# Main.net
KiCad netlist of a schematic drawn in Altium Designer
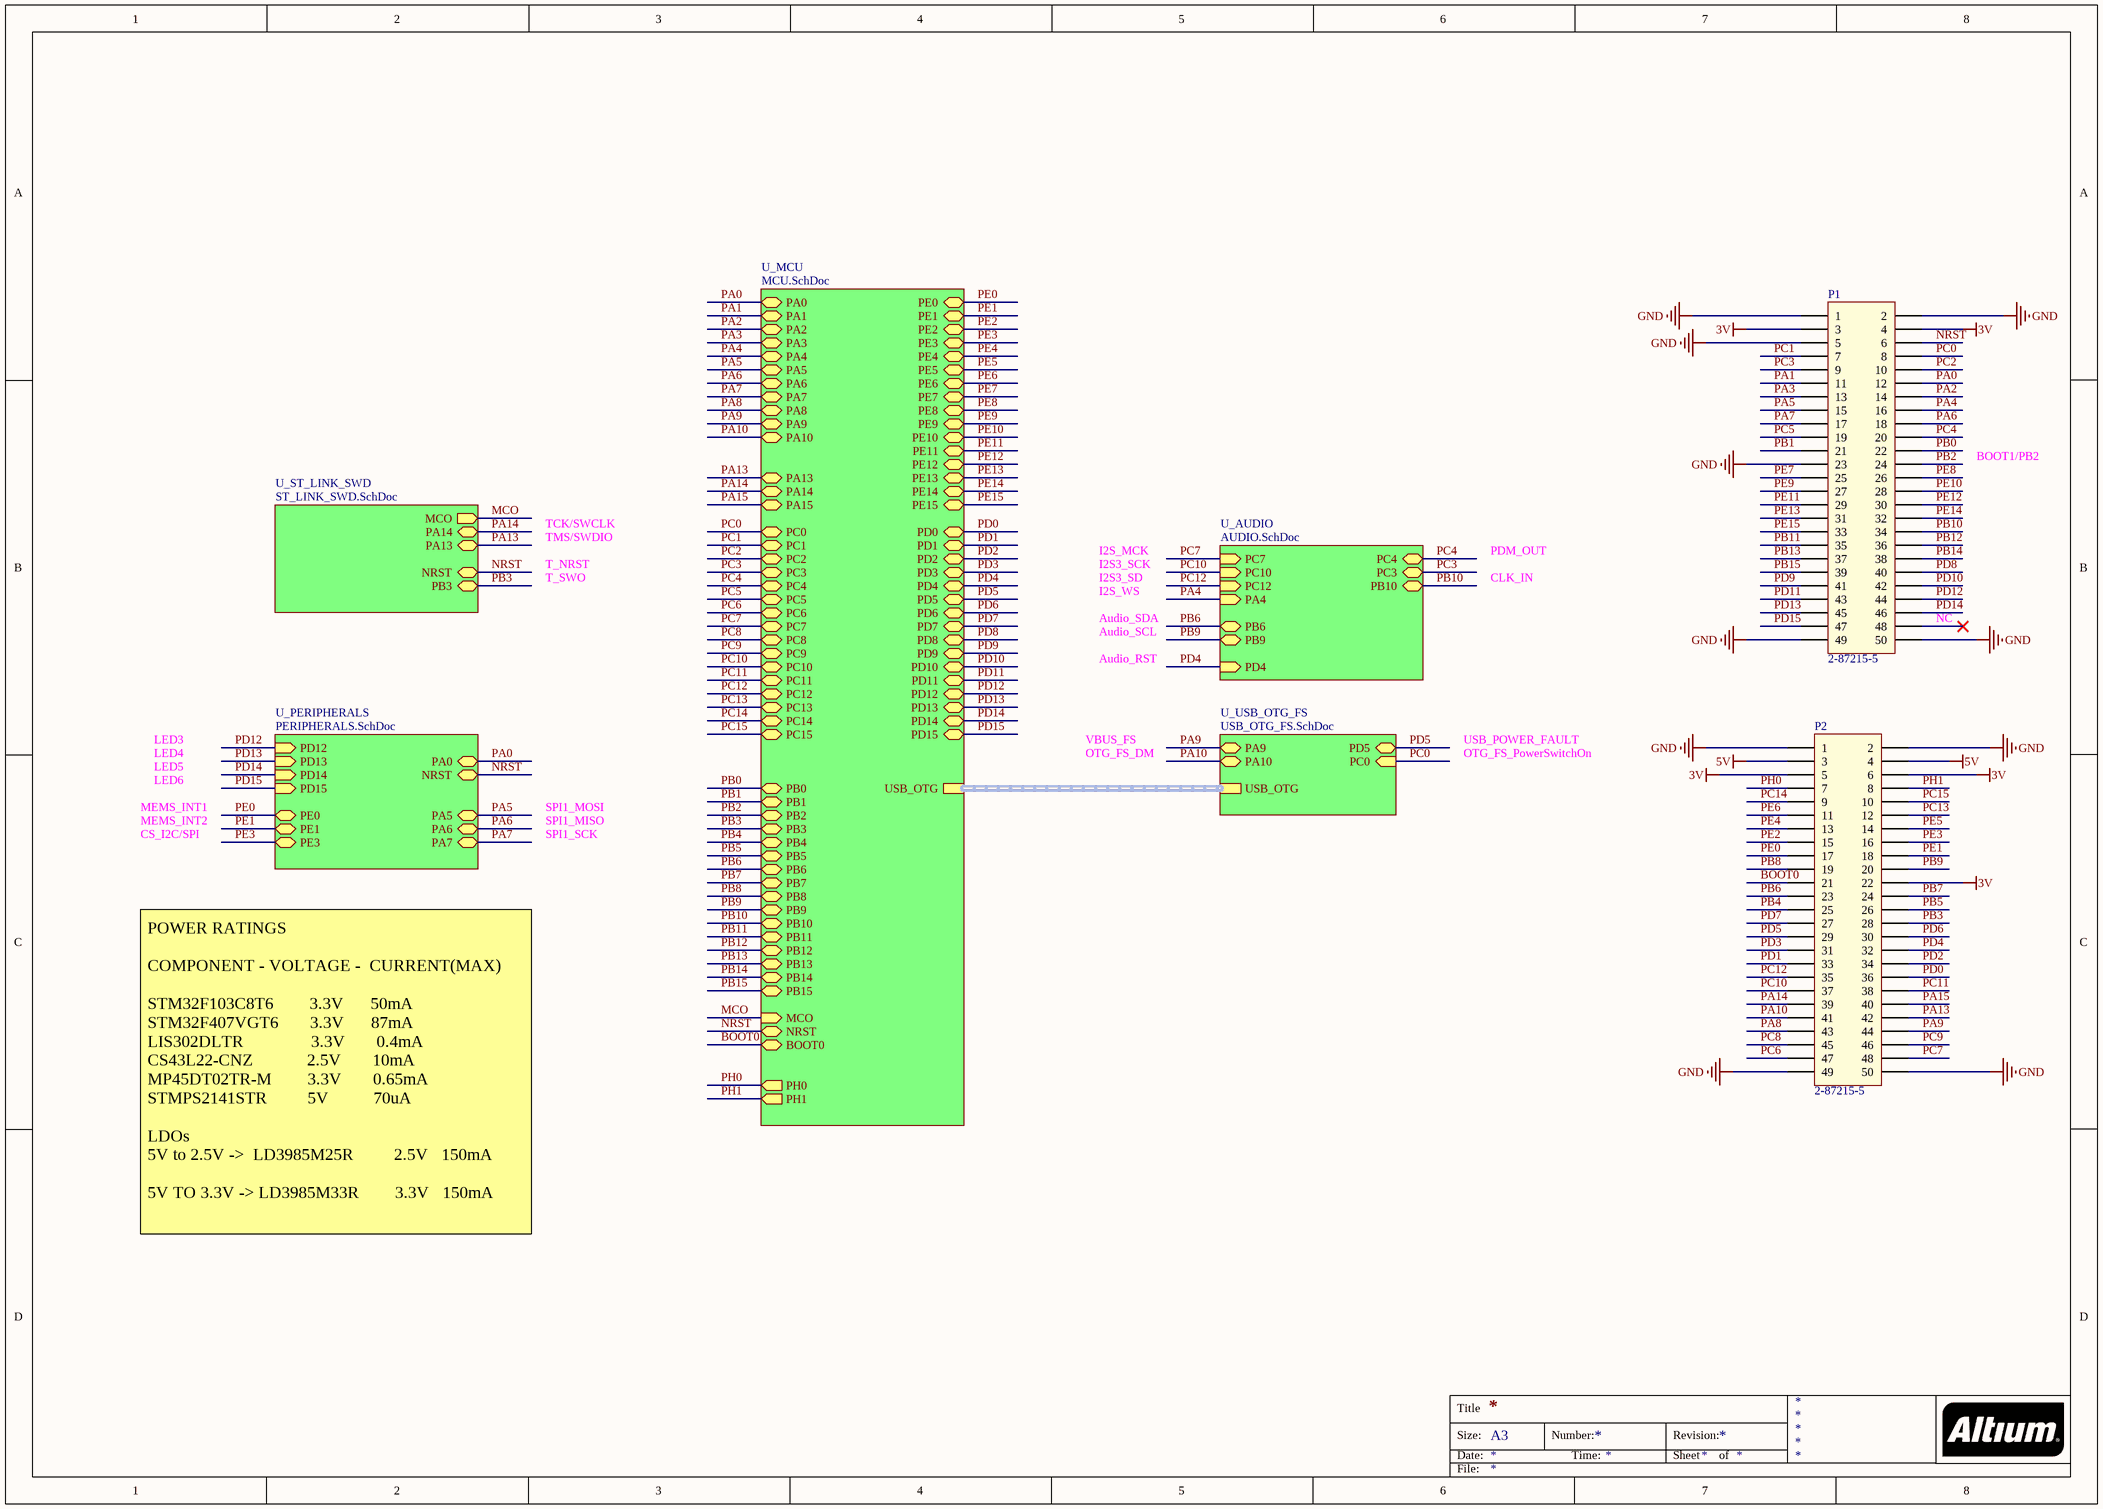
[diagram p0: Main.SchDoc]

(export (version "E")
  (design (tool "Eeschema 10.0.6"))
  (components
    (comp (ref "P1")
      (value "2-87215-5")
      (footprint "HEADER 25x2")
      (fields (field (name "MANUFACTURER") "TE Connectivity (Tyco Electronics)"))
      (libsource (lib "STM32F4DISCOVERY") (part "2-87215-5"))
    )
    (comp (ref "P2")
      (value "2-87215-5")
      (footprint "HEADER 25x2")
      (fields (field (name "MANUFACTURER") "TE Connectivity (Tyco Electronics)"))
      (libsource (lib "STM32F4DISCOVERY") (part "2-87215-5"))
    )
  )
  (nets
    (net (code "1") (name "/BOOT0") (class "Default")
      (node (ref "P2") (pin "21") (pinfunction "21_21") (pintype "passive"))
    )
    (net (code "3") (name "/NRST") (class "Default")
      (node (ref "P1") (pin "6") (pinfunction "6_6") (pintype "passive"))
    )
    (net (code "4") (name "/PA0") (class "Default")
      (node (ref "P1") (pin "12") (pinfunction "12_12") (pintype "passive"))
    )
    (net (code "5") (name "/PA1") (class "Default")
      (node (ref "P1") (pin "11") (pinfunction "11_11") (pintype "passive"))
    )
    (net (code "6") (name "/PA2") (class "Default")
      (node (ref "P1") (pin "14") (pinfunction "14_14") (pintype "passive"))
    )
    (net (code "7") (name "/PA3") (class "Default")
      (node (ref "P1") (pin "13") (pinfunction "13_13") (pintype "passive"))
    )
    (net (code "8") (name "/PA4") (class "Default")
      (node (ref "P1") (pin "16") (pinfunction "16_16") (pintype "passive"))
    )
    (net (code "9") (name "/PA5") (class "Default")
      (node (ref "P1") (pin "15") (pinfunction "15_15") (pintype "passive"))
    )
    (net (code "10") (name "/PA6") (class "Default")
      (node (ref "P1") (pin "18") (pinfunction "18_18") (pintype "passive"))
    )
    (net (code "11") (name "/PA7") (class "Default")
      (node (ref "P1") (pin "17") (pinfunction "17_17") (pintype "passive"))
    )
    (net (code "12") (name "/PA8") (class "Default")
      (node (ref "P2") (pin "43") (pinfunction "43_43") (pintype "passive"))
    )
    (net (code "13") (name "/PA9") (class "Default")
      (node (ref "P2") (pin "44") (pinfunction "44_44") (pintype "passive"))
    )
    (net (code "14") (name "/PA10") (class "Default")
      (node (ref "P2") (pin "41") (pinfunction "41_41") (pintype "passive"))
    )
    (net (code "15") (name "/PA13") (class "Default")
      (node (ref "P2") (pin "42") (pinfunction "42_42") (pintype "passive"))
    )
    (net (code "16") (name "/PA14") (class "Default")
      (node (ref "P2") (pin "39") (pinfunction "39_39") (pintype "passive"))
    )
    (net (code "17") (name "/PA15") (class "Default")
      (node (ref "P2") (pin "40") (pinfunction "40_40") (pintype "passive"))
    )
    (net (code "18") (name "/PB0") (class "Default")
      (node (ref "P1") (pin "22") (pinfunction "22_22") (pintype "passive"))
    )
    (net (code "19") (name "/PB1") (class "Default")
      (node (ref "P1") (pin "21") (pinfunction "21_21") (pintype "passive"))
    )
    (net (code "20") (name "/PB2") (class "Default")
      (node (ref "P1") (pin "24") (pinfunction "24_24") (pintype "passive"))
    )
    (net (code "21") (name "/PB3") (class "Default")
      (node (ref "P2") (pin "28") (pinfunction "28_28") (pintype "passive"))
    )
    (net (code "22") (name "/PB4") (class "Default")
      (node (ref "P2") (pin "25") (pinfunction "25_25") (pintype "passive"))
    )
    (net (code "23") (name "/PB5") (class "Default")
      (node (ref "P2") (pin "26") (pinfunction "26_26") (pintype "passive"))
    )
    (net (code "24") (name "/PB6") (class "Default")
      (node (ref "P2") (pin "23") (pinfunction "23_23") (pintype "passive"))
    )
    (net (code "25") (name "/PB7") (class "Default")
      (node (ref "P2") (pin "24") (pinfunction "24_24") (pintype "passive"))
    )
    (net (code "26") (name "/PB8") (class "Default")
      (node (ref "P2") (pin "19") (pinfunction "19_19") (pintype "passive"))
    )
    (net (code "27") (name "/PB9") (class "Default")
      (node (ref "P2") (pin "20") (pinfunction "20_20") (pintype "passive"))
    )
    (net (code "28") (name "/PB10") (class "Default")
      (node (ref "P1") (pin "34") (pinfunction "34_34") (pintype "passive"))
    )
    (net (code "29") (name "/PB11") (class "Default")
      (node (ref "P1") (pin "35") (pinfunction "35_35") (pintype "passive"))
    )
    (net (code "30") (name "/PB12") (class "Default")
      (node (ref "P1") (pin "36") (pinfunction "36_36") (pintype "passive"))
    )
    (net (code "31") (name "/PB13") (class "Default")
      (node (ref "P1") (pin "37") (pinfunction "37_37") (pintype "passive"))
    )
    (net (code "32") (name "/PB14") (class "Default")
      (node (ref "P1") (pin "38") (pinfunction "38_38") (pintype "passive"))
    )
    (net (code "33") (name "/PB15") (class "Default")
      (node (ref "P1") (pin "39") (pinfunction "39_39") (pintype "passive"))
    )
    (net (code "34") (name "/PC0") (class "Default")
      (node (ref "P1") (pin "8") (pinfunction "8_8") (pintype "passive"))
    )
    (net (code "35") (name "/PC1") (class "Default")
      (node (ref "P1") (pin "7") (pinfunction "7_7") (pintype "passive"))
    )
    (net (code "36") (name "/PC2") (class "Default")
      (node (ref "P1") (pin "10") (pinfunction "10_10") (pintype "passive"))
    )
    (net (code "37") (name "/PC3") (class "Default")
      (node (ref "P1") (pin "9") (pinfunction "9_9") (pintype "passive"))
    )
    (net (code "38") (name "/PC4") (class "Default")
      (node (ref "P1") (pin "20") (pinfunction "20_20") (pintype "passive"))
    )
    (net (code "39") (name "/PC5") (class "Default")
      (node (ref "P1") (pin "19") (pinfunction "19_19") (pintype "passive"))
    )
    (net (code "40") (name "/PC6") (class "Default")
      (node (ref "P2") (pin "47") (pinfunction "47_47") (pintype "passive"))
    )
    (net (code "41") (name "/PC7") (class "Default")
      (node (ref "P2") (pin "48") (pinfunction "48_48") (pintype "passive"))
    )
    (net (code "42") (name "/PC8") (class "Default")
      (node (ref "P2") (pin "45") (pinfunction "45_45") (pintype "passive"))
    )
    (net (code "43") (name "/PC9") (class "Default")
      (node (ref "P2") (pin "46") (pinfunction "46_46") (pintype "passive"))
    )
    (net (code "44") (name "/PC10") (class "Default")
      (node (ref "P2") (pin "37") (pinfunction "37_37") (pintype "passive"))
    )
    (net (code "45") (name "/PC11") (class "Default")
      (node (ref "P2") (pin "38") (pinfunction "38_38") (pintype "passive"))
    )
    (net (code "46") (name "/PC12") (class "Default")
      (node (ref "P2") (pin "35") (pinfunction "35_35") (pintype "passive"))
    )
    (net (code "47") (name "/PC13") (class "Default")
      (node (ref "P2") (pin "12") (pinfunction "12_12") (pintype "passive"))
    )
    (net (code "48") (name "/PC14") (class "Default")
      (node (ref "P2") (pin "9") (pinfunction "9_9") (pintype "passive"))
    )
    (net (code "49") (name "/PC15") (class "Default")
      (node (ref "P2") (pin "10") (pinfunction "10_10") (pintype "passive"))
    )
    (net (code "50") (name "/PD0") (class "Default")
      (node (ref "P2") (pin "36") (pinfunction "36_36") (pintype "passive"))
    )
    (net (code "51") (name "/PD1") (class "Default")
      (node (ref "P2") (pin "33") (pinfunction "33_33") (pintype "passive"))
    )
    (net (code "52") (name "/PD2") (class "Default")
      (node (ref "P2") (pin "34") (pinfunction "34_34") (pintype "passive"))
    )
    (net (code "53") (name "/PD3") (class "Default")
      (node (ref "P2") (pin "31") (pinfunction "31_31") (pintype "passive"))
    )
    (net (code "54") (name "/PD4") (class "Default")
      (node (ref "P2") (pin "32") (pinfunction "32_32") (pintype "passive"))
    )
    (net (code "55") (name "/PD5") (class "Default")
      (node (ref "P2") (pin "29") (pinfunction "29_29") (pintype "passive"))
    )
    (net (code "56") (name "/PD6") (class "Default")
      (node (ref "P2") (pin "30") (pinfunction "30_30") (pintype "passive"))
    )
    (net (code "57") (name "/PD7") (class "Default")
      (node (ref "P2") (pin "27") (pinfunction "27_27") (pintype "passive"))
    )
    (net (code "58") (name "/PD8") (class "Default")
      (node (ref "P1") (pin "40") (pinfunction "40_40") (pintype "passive"))
    )
    (net (code "59") (name "/PD9") (class "Default")
      (node (ref "P1") (pin "41") (pinfunction "41_41") (pintype "passive"))
    )
    (net (code "60") (name "/PD10") (class "Default")
      (node (ref "P1") (pin "42") (pinfunction "42_42") (pintype "passive"))
    )
    (net (code "61") (name "/PD11") (class "Default")
      (node (ref "P1") (pin "43") (pinfunction "43_43") (pintype "passive"))
    )
    (net (code "62") (name "/PD12") (class "Default")
      (node (ref "P1") (pin "44") (pinfunction "44_44") (pintype "passive"))
    )
    (net (code "63") (name "/PD13") (class "Default")
      (node (ref "P1") (pin "45") (pinfunction "45_45") (pintype "passive"))
    )
    (net (code "64") (name "/PD14") (class "Default")
      (node (ref "P1") (pin "46") (pinfunction "46_46") (pintype "passive"))
    )
    (net (code "65") (name "/PD15") (class "Default")
      (node (ref "P1") (pin "47") (pinfunction "47_47") (pintype "passive"))
    )
    (net (code "66") (name "/PE0") (class "Default")
      (node (ref "P2") (pin "17") (pinfunction "17_17") (pintype "passive"))
    )
    (net (code "67") (name "/PE1") (class "Default")
      (node (ref "P2") (pin "18") (pinfunction "18_18") (pintype "passive"))
    )
    (net (code "68") (name "/PE2") (class "Default")
      (node (ref "P2") (pin "15") (pinfunction "15_15") (pintype "passive"))
    )
    (net (code "69") (name "/PE3") (class "Default")
      (node (ref "P2") (pin "16") (pinfunction "16_16") (pintype "passive"))
    )
    (net (code "70") (name "/PE4") (class "Default")
      (node (ref "P2") (pin "13") (pinfunction "13_13") (pintype "passive"))
    )
    (net (code "71") (name "/PE5") (class "Default")
      (node (ref "P2") (pin "14") (pinfunction "14_14") (pintype "passive"))
    )
    (net (code "72") (name "/PE6") (class "Default")
      (node (ref "P2") (pin "11") (pinfunction "11_11") (pintype "passive"))
    )
    (net (code "73") (name "/PE7") (class "Default")
      (node (ref "P1") (pin "25") (pinfunction "25_25") (pintype "passive"))
    )
    (net (code "74") (name "/PE8") (class "Default")
      (node (ref "P1") (pin "26") (pinfunction "26_26") (pintype "passive"))
    )
    (net (code "75") (name "/PE9") (class "Default")
      (node (ref "P1") (pin "27") (pinfunction "27_27") (pintype "passive"))
    )
    (net (code "76") (name "/PE10") (class "Default")
      (node (ref "P1") (pin "28") (pinfunction "28_28") (pintype "passive"))
    )
    (net (code "77") (name "/PE11") (class "Default")
      (node (ref "P1") (pin "29") (pinfunction "29_29") (pintype "passive"))
    )
    (net (code "78") (name "/PE12") (class "Default")
      (node (ref "P1") (pin "30") (pinfunction "30_30") (pintype "passive"))
    )
    (net (code "79") (name "/PE13") (class "Default")
      (node (ref "P1") (pin "31") (pinfunction "31_31") (pintype "passive"))
    )
    (net (code "80") (name "/PE14") (class "Default")
      (node (ref "P1") (pin "32") (pinfunction "32_32") (pintype "passive"))
    )
    (net (code "81") (name "/PE15") (class "Default")
      (node (ref "P1") (pin "33") (pinfunction "33_33") (pintype "passive"))
    )
    (net (code "82") (name "/PH0") (class "Default")
      (node (ref "P2") (pin "7") (pinfunction "7_7") (pintype "passive"))
    )
    (net (code "83") (name "/PH1") (class "Default")
      (node (ref "P2") (pin "8") (pinfunction "8_8") (pintype "passive"))
    )
    (net (code "85") (name "3V") (class "Default")
      (node (ref "P1") (pin "3") (pinfunction "3_3") (pintype "passive"))
      (node (ref "P1") (pin "4") (pinfunction "4_4") (pintype "passive"))
      (node (ref "P2") (pin "22") (pinfunction "22_22") (pintype "passive"))
      (node (ref "P2") (pin "5") (pinfunction "5_5") (pintype "passive"))
      (node (ref "P2") (pin "6") (pinfunction "6_6") (pintype "passive"))
    )
    (net (code "86") (name "5V") (class "Default")
      (node (ref "P2") (pin "3") (pinfunction "3_3") (pintype "passive"))
      (node (ref "P2") (pin "4") (pinfunction "4_4") (pintype "passive"))
    )
    (net (code "87") (name "GND") (class "Default")
      (node (ref "P1") (pin "1") (pinfunction "1_1") (pintype "passive"))
      (node (ref "P1") (pin "2") (pinfunction "2_2") (pintype "passive"))
      (node (ref "P1") (pin "23") (pinfunction "23_23") (pintype "passive"))
      (node (ref "P1") (pin "49") (pinfunction "49_49") (pintype "passive"))
      (node (ref "P1") (pin "5") (pinfunction "5_5") (pintype "passive"))
      (node (ref "P1") (pin "50") (pinfunction "50_50") (pintype "passive"))
      (node (ref "P2") (pin "1") (pinfunction "1_1") (pintype "passive"))
      (node (ref "P2") (pin "2") (pinfunction "2_2") (pintype "passive"))
      (node (ref "P2") (pin "49") (pinfunction "49_49") (pintype "passive"))
      (node (ref "P2") (pin "50") (pinfunction "50_50") (pintype "passive"))
    )
    (net (code "88") (name "unconnected-(P1-Pad48)") (class "Default")
      (node (ref "P1") (pin "48") (pinfunction "48_48") (pintype "passive+no_connect"))
    )
  )
)
